# MainBoard_v1_4.net
KiCad netlist of a schematic drawn in EAGLE
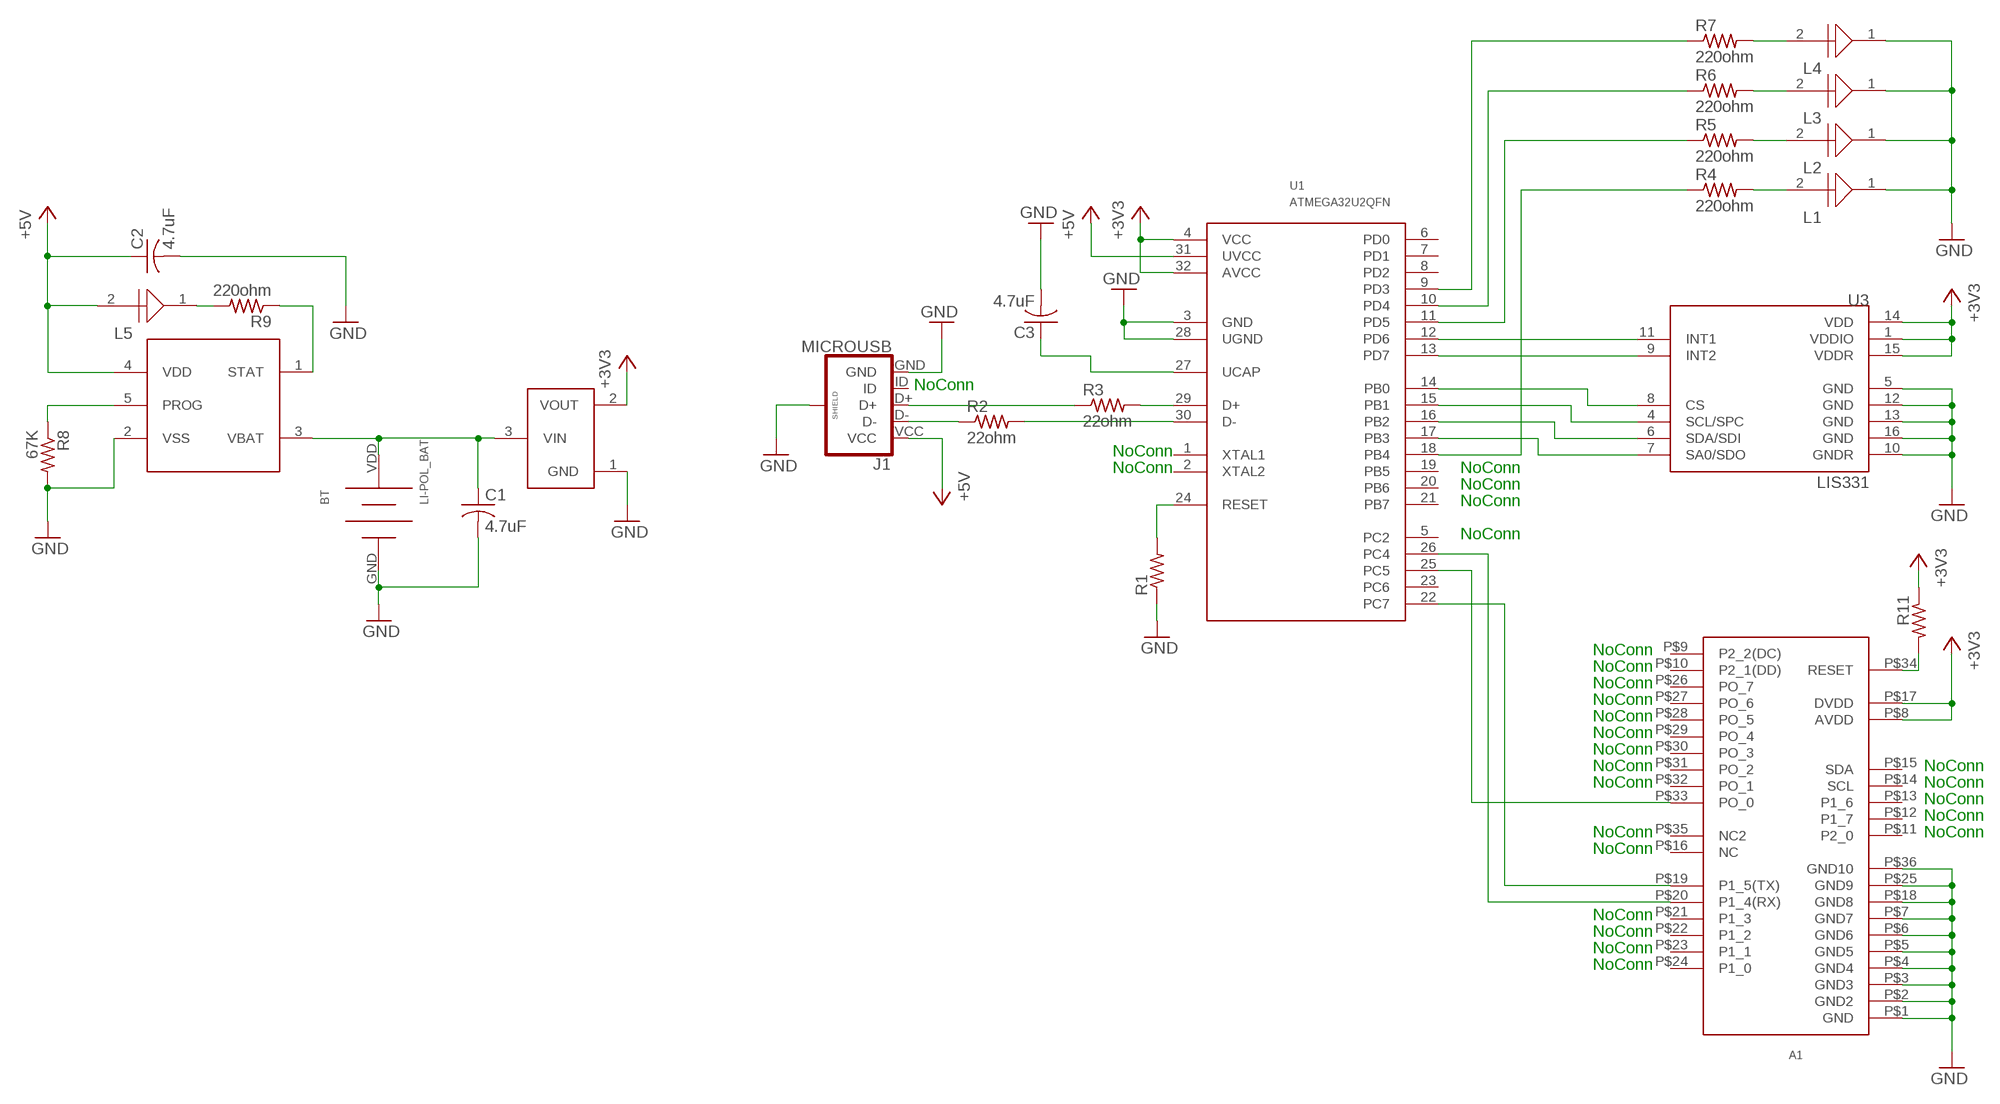
[diagram p0: schematic, sheet 1]

(export (version "E")
  (design (tool "Eeschema 10.0.6"))
  (components
    (comp (ref "A1")
      (value "BLE113-A")
      (footprint "eagle-import:BLUETOOTHNS")
      (libsource (lib "eagle-import") (part "BLE113-A"))
    )
    (comp (ref "BT")
      (value "LI-POL_BAT")
      (footprint "eagle-import:LI-POLY_28")
      (libsource (lib "eagle-import") (part "LI-POL_BAT"))
    )
    (comp (ref "C1")
      (value "4.7uF")
      (footprint "eagle-import:C0402")
      (libsource (lib "eagle-import") (part "C-USC0402"))
    )
    (comp (ref "C2")
      (value "4.7uF")
      (footprint "eagle-import:C0402")
      (libsource (lib "eagle-import") (part "C-USC0402"))
    )
    (comp (ref "C3")
      (value "4.7uF")
      (footprint "eagle-import:C0402")
      (libsource (lib "eagle-import") (part "C-USC0402"))
    )
    (comp (ref "J1")
      (value "MICROUSB")
      (footprint "eagle-import:MICROUSB")
      (libsource (lib "eagle-import") (part "MICROUSB"))
    )
    (comp (ref "L1")
      (value "LED_0402")
      (footprint "eagle-import:R0402")
      (libsource (lib "eagle-import") (part "LED_0402"))
    )
    (comp (ref "L2")
      (value "LED_0402")
      (footprint "eagle-import:R0402")
      (libsource (lib "eagle-import") (part "LED_0402"))
    )
    (comp (ref "L3")
      (value "LED_0402")
      (footprint "eagle-import:R0402")
      (libsource (lib "eagle-import") (part "LED_0402"))
    )
    (comp (ref "L4")
      (value "LED_0402")
      (footprint "eagle-import:R0402")
      (libsource (lib "eagle-import") (part "LED_0402"))
    )
    (comp (ref "L5")
      (value "LED_0402")
      (footprint "eagle-import:R0402")
      (libsource (lib "eagle-import") (part "LED_0402"))
    )
    (comp (ref "R1")
      (value "R-US_R0402")
      (footprint "eagle-import:R0402")
      (libsource (lib "eagle-import") (part "R-US_R0402"))
    )
    (comp (ref "R2")
      (value "22ohm")
      (footprint "eagle-import:R0402")
      (libsource (lib "eagle-import") (part "R-US_R0402"))
    )
    (comp (ref "R3")
      (value "22ohm")
      (footprint "eagle-import:R0402")
      (libsource (lib "eagle-import") (part "R-US_R0402"))
    )
    (comp (ref "R4")
      (value "220ohm")
      (footprint "eagle-import:R0402")
      (libsource (lib "eagle-import") (part "R-US_R0402"))
    )
    (comp (ref "R5")
      (value "220ohm")
      (footprint "eagle-import:R0402")
      (libsource (lib "eagle-import") (part "R-US_R0402"))
    )
    (comp (ref "R6")
      (value "220ohm")
      (footprint "eagle-import:R0402")
      (libsource (lib "eagle-import") (part "R-US_R0402"))
    )
    (comp (ref "R7")
      (value "220ohm")
      (footprint "eagle-import:R0402")
      (libsource (lib "eagle-import") (part "R-US_R0402"))
    )
    (comp (ref "R8")
      (value "67K")
      (footprint "eagle-import:R0402")
      (libsource (lib "eagle-import") (part "R-US_R0402"))
    )
    (comp (ref "R9")
      (value "220ohm")
      (footprint "eagle-import:R0402")
      (libsource (lib "eagle-import") (part "R-US_R0402"))
    )
    (comp (ref "R11")
      (value "R-US_R0402")
      (footprint "eagle-import:R0402")
      (libsource (lib "eagle-import") (part "R-US_R0402"))
    )
    (comp (ref "U1")
      (value "ATMEGA32U2QFN")
      (footprint "eagle-import:QFN-32")
      (libsource (lib "eagle-import") (part "ATMEGA32U2QFN"))
    )
    (comp (ref "U2")
      (value "MCP738312")
      (footprint "eagle-import:SOT23-5")
      (libsource (lib "eagle-import") (part "MCP738312"))
    )
    (comp (ref "U3")
      (value "LIS331")
      (footprint "eagle-import:LGA16-3MM")
      (libsource (lib "eagle-import") (part "LIS331"))
    )
    (comp (ref "U5")
      (value "REGULATOR")
      (footprint "eagle-import:SOT23-3")
      (libsource (lib "eagle-import") (part "REGULATOR"))
    )
  )
  (nets
    (net (code "1") (name "+3V3") (class "Default")
      (node (ref "A1") (pin "P$17") (pinfunction "DVDD_P$17") (pintype "bidirectional"))
      (node (ref "A1") (pin "P$8") (pinfunction "AVDD_P$8") (pintype "bidirectional"))
      (node (ref "R11") (pin "1") (pinfunction "1_1") (pintype "passive"))
      (node (ref "U1") (pin "32") (pinfunction "AVCC_32") (pintype "bidirectional"))
      (node (ref "U1") (pin "4") (pinfunction "VCC_4") (pintype "bidirectional"))
      (node (ref "U3") (pin "1") (pinfunction "VDDIO_1") (pintype "bidirectional"))
      (node (ref "U3") (pin "14") (pinfunction "VDD_14") (pintype "bidirectional"))
      (node (ref "U3") (pin "15") (pinfunction "VDDR_15") (pintype "bidirectional"))
      (node (ref "U5") (pin "2") (pinfunction "VOUT_2") (pintype "bidirectional"))
    )
    (net (code "2") (name "+5V") (class "Default")
      (node (ref "C2") (pin "1") (pinfunction "1_1") (pintype "passive"))
      (node (ref "J1") (pin "VCC") (pinfunction "VCC_VCC") (pintype "bidirectional"))
      (node (ref "L5") (pin "2") (pinfunction "P2_2") (pintype "bidirectional"))
      (node (ref "U1") (pin "31") (pinfunction "UVCC_31") (pintype "bidirectional"))
      (node (ref "U2") (pin "4") (pinfunction "VDD_4") (pintype "bidirectional"))
    )
    (net (code "3") (name "GND") (class "Default")
      (node (ref "A1") (pin "P$1") (pinfunction "GND_P$1") (pintype "bidirectional"))
      (node (ref "A1") (pin "P$18") (pinfunction "GND8_P$18") (pintype "bidirectional"))
      (node (ref "A1") (pin "P$2") (pinfunction "GND2_P$2") (pintype "bidirectional"))
      (node (ref "A1") (pin "P$25") (pinfunction "GND9_P$25") (pintype "bidirectional"))
      (node (ref "A1") (pin "P$3") (pinfunction "GND3_P$3") (pintype "bidirectional"))
      (node (ref "A1") (pin "P$36") (pinfunction "GND10_P$36") (pintype "bidirectional"))
      (node (ref "A1") (pin "P$4") (pinfunction "GND4_P$4") (pintype "bidirectional"))
      (node (ref "A1") (pin "P$5") (pinfunction "GND5_P$5") (pintype "bidirectional"))
      (node (ref "A1") (pin "P$6") (pinfunction "GND6_P$6") (pintype "bidirectional"))
      (node (ref "A1") (pin "P$7") (pinfunction "GND7_P$7") (pintype "bidirectional"))
      (node (ref "BT") (pin "GND") (pinfunction "GND_GND") (pintype "bidirectional"))
      (node (ref "C1") (pin "2") (pinfunction "2_2") (pintype "passive"))
      (node (ref "C2") (pin "2") (pinfunction "2_2") (pintype "passive"))
      (node (ref "C3") (pin "2") (pinfunction "2_2") (pintype "passive"))
      (node (ref "J1") (pin "GD1") (pinfunction "SHIELD_GD1") (pintype "bidirectional"))
      (node (ref "J1") (pin "GD2") (pinfunction "SHIELD_GD2") (pintype "bidirectional"))
      (node (ref "J1") (pin "GD3") (pinfunction "SHIELD_GD3") (pintype "bidirectional"))
      (node (ref "J1") (pin "GD4") (pinfunction "SHIELD_GD4") (pintype "bidirectional"))
      (node (ref "J1") (pin "GND") (pinfunction "GND_GND") (pintype "bidirectional"))
      (node (ref "L1") (pin "1") (pinfunction "P1_1") (pintype "bidirectional"))
      (node (ref "L2") (pin "1") (pinfunction "P1_1") (pintype "bidirectional"))
      (node (ref "L3") (pin "1") (pinfunction "P1_1") (pintype "bidirectional"))
      (node (ref "L4") (pin "1") (pinfunction "P1_1") (pintype "bidirectional"))
      (node (ref "R1") (pin "1") (pinfunction "1_1") (pintype "passive"))
      (node (ref "R8") (pin "2") (pinfunction "2_2") (pintype "passive"))
      (node (ref "U1") (pin "28") (pinfunction "UGND_28") (pintype "bidirectional"))
      (node (ref "U1") (pin "3") (pinfunction "GND_3") (pintype "bidirectional"))
      (node (ref "U2") (pin "2") (pinfunction "VSS_2") (pintype "bidirectional"))
      (node (ref "U3") (pin "10") (pinfunction "GNDR_10") (pintype "bidirectional"))
      (node (ref "U3") (pin "12") (pinfunction "GND_12") (pintype "bidirectional"))
      (node (ref "U3") (pin "13") (pinfunction "GND_13") (pintype "bidirectional"))
      (node (ref "U3") (pin "16") (pinfunction "GND_16") (pintype "bidirectional"))
      (node (ref "U3") (pin "5") (pinfunction "GND_5") (pintype "bidirectional"))
      (node (ref "U5") (pin "1") (pinfunction "GND_1") (pintype "bidirectional"))
    )
    (net (code "4") (name "Net-(A1-P1_4(RX))") (class "Default")
      (node (ref "A1") (pin "P$20") (pinfunction "P1_4(RX)_P$20") (pintype "bidirectional"))
      (node (ref "U1") (pin "26") (pinfunction "PC4_26") (pintype "bidirectional"))
    )
    (net (code "5") (name "Net-(A1-P1_5(TX))") (class "Default")
      (node (ref "A1") (pin "P$19") (pinfunction "P1_5(TX)_P$19") (pintype "bidirectional"))
      (node (ref "U1") (pin "22") (pinfunction "PC7_22") (pintype "bidirectional"))
    )
    (net (code "6") (name "Net-(A1-PO_0)") (class "Default")
      (node (ref "A1") (pin "P$33") (pinfunction "PO_0_P$33") (pintype "bidirectional"))
      (node (ref "U1") (pin "25") (pinfunction "PC5_25") (pintype "bidirectional"))
    )
    (net (code "7") (name "Net-(A1-RESET)") (class "Default")
      (node (ref "A1") (pin "P$34") (pinfunction "RESET_P$34") (pintype "bidirectional"))
      (node (ref "R11") (pin "2") (pinfunction "2_2") (pintype "passive"))
    )
    (net (code "8") (name "Net-(J1-PadD+)") (class "Default")
      (node (ref "J1") (pin "D+") (pinfunction "D+_D+") (pintype "bidirectional"))
      (node (ref "R3") (pin "1") (pinfunction "1_1") (pintype "passive"))
    )
    (net (code "9") (name "Net-(J1-PadD-)") (class "Default")
      (node (ref "J1") (pin "D-") (pinfunction "D-_D-") (pintype "bidirectional"))
      (node (ref "R2") (pin "1") (pinfunction "1_1") (pintype "passive"))
    )
    (net (code "10") (name "Net-(L1-P2)") (class "Default")
      (node (ref "L1") (pin "2") (pinfunction "P2_2") (pintype "bidirectional"))
      (node (ref "R4") (pin "2") (pinfunction "2_2") (pintype "passive"))
    )
    (net (code "11") (name "Net-(L2-P2)") (class "Default")
      (node (ref "L2") (pin "2") (pinfunction "P2_2") (pintype "bidirectional"))
      (node (ref "R5") (pin "2") (pinfunction "2_2") (pintype "passive"))
    )
    (net (code "12") (name "Net-(L3-P2)") (class "Default")
      (node (ref "L3") (pin "2") (pinfunction "P2_2") (pintype "bidirectional"))
      (node (ref "R6") (pin "2") (pinfunction "2_2") (pintype "passive"))
    )
    (net (code "13") (name "Net-(L4-P2)") (class "Default")
      (node (ref "L4") (pin "2") (pinfunction "P2_2") (pintype "bidirectional"))
      (node (ref "R7") (pin "2") (pinfunction "2_2") (pintype "passive"))
    )
    (net (code "14") (name "Net-(L5-P1)") (class "Default")
      (node (ref "L5") (pin "1") (pinfunction "P1_1") (pintype "bidirectional"))
      (node (ref "R9") (pin "2") (pinfunction "2_2") (pintype "passive"))
    )
    (net (code "15") (name "Net-(U1-D+)") (class "Default")
      (node (ref "R3") (pin "2") (pinfunction "2_2") (pintype "passive"))
      (node (ref "U1") (pin "29") (pinfunction "D+_29") (pintype "bidirectional"))
    )
    (net (code "16") (name "Net-(U1-D-)") (class "Default")
      (node (ref "R2") (pin "2") (pinfunction "2_2") (pintype "passive"))
      (node (ref "U1") (pin "30") (pinfunction "D-_30") (pintype "bidirectional"))
    )
    (net (code "17") (name "Net-(U1-PB0)") (class "Default")
      (node (ref "U1") (pin "14") (pinfunction "PB0_14") (pintype "bidirectional"))
      (node (ref "U3") (pin "8") (pinfunction "CS_8") (pintype "bidirectional"))
    )
    (net (code "18") (name "Net-(U1-PB1)") (class "Default")
      (node (ref "U1") (pin "15") (pinfunction "PB1_15") (pintype "bidirectional"))
      (node (ref "U3") (pin "4") (pinfunction "SCL/SPC_4") (pintype "bidirectional"))
    )
    (net (code "19") (name "Net-(U1-PB2)") (class "Default")
      (node (ref "U1") (pin "16") (pinfunction "PB2_16") (pintype "bidirectional"))
      (node (ref "U3") (pin "6") (pinfunction "SDA/SDI_6") (pintype "bidirectional"))
    )
    (net (code "20") (name "Net-(U1-PB3)") (class "Default")
      (node (ref "U1") (pin "17") (pinfunction "PB3_17") (pintype "bidirectional"))
      (node (ref "U3") (pin "7") (pinfunction "SA0/SDO_7") (pintype "bidirectional"))
    )
    (net (code "21") (name "Net-(U1-PB4)") (class "Default")
      (node (ref "R4") (pin "1") (pinfunction "1_1") (pintype "passive"))
      (node (ref "U1") (pin "18") (pinfunction "PB4_18") (pintype "bidirectional"))
    )
    (net (code "22") (name "Net-(U1-PD3)") (class "Default")
      (node (ref "R7") (pin "1") (pinfunction "1_1") (pintype "passive"))
      (node (ref "U1") (pin "9") (pinfunction "PD3_9") (pintype "bidirectional"))
    )
    (net (code "23") (name "Net-(U1-PD4)") (class "Default")
      (node (ref "R6") (pin "1") (pinfunction "1_1") (pintype "passive"))
      (node (ref "U1") (pin "10") (pinfunction "PD4_10") (pintype "bidirectional"))
    )
    (net (code "24") (name "Net-(U1-PD5)") (class "Default")
      (node (ref "R5") (pin "1") (pinfunction "1_1") (pintype "passive"))
      (node (ref "U1") (pin "11") (pinfunction "PD5_11") (pintype "bidirectional"))
    )
    (net (code "25") (name "Net-(U1-PD6)") (class "Default")
      (node (ref "U1") (pin "12") (pinfunction "PD6_12") (pintype "bidirectional"))
      (node (ref "U3") (pin "11") (pinfunction "INT1_11") (pintype "bidirectional"))
    )
    (net (code "26") (name "Net-(U1-PD7)") (class "Default")
      (node (ref "U1") (pin "13") (pinfunction "PD7_13") (pintype "bidirectional"))
      (node (ref "U3") (pin "9") (pinfunction "INT2_9") (pintype "bidirectional"))
    )
    (net (code "27") (name "Net-(U1-RESET)") (class "Default")
      (node (ref "R1") (pin "2") (pinfunction "2_2") (pintype "passive"))
      (node (ref "U1") (pin "24") (pinfunction "RESET_24") (pintype "bidirectional"))
    )
    (net (code "28") (name "Net-(U1-UCAP)") (class "Default")
      (node (ref "C3") (pin "1") (pinfunction "1_1") (pintype "passive"))
      (node (ref "U1") (pin "27") (pinfunction "UCAP_27") (pintype "bidirectional"))
    )
    (net (code "29") (name "Net-(U2-PROG)") (class "Default")
      (node (ref "R8") (pin "1") (pinfunction "1_1") (pintype "passive"))
      (node (ref "U2") (pin "5") (pinfunction "PROG_5") (pintype "bidirectional"))
    )
    (net (code "30") (name "Net-(U2-STAT)") (class "Default")
      (node (ref "R9") (pin "1") (pinfunction "1_1") (pintype "passive"))
      (node (ref "U2") (pin "1") (pinfunction "STAT_1") (pintype "bidirectional"))
    )
    (net (code "31") (name "Net-(U2-VBAT)") (class "Default")
      (node (ref "BT") (pin "VDD") (pinfunction "VDD_VDD") (pintype "bidirectional"))
      (node (ref "C1") (pin "1") (pinfunction "1_1") (pintype "passive"))
      (node (ref "U2") (pin "3") (pinfunction "VBAT_3") (pintype "bidirectional"))
      (node (ref "U5") (pin "3") (pinfunction "VIN_3") (pintype "bidirectional"))
    )
    (net (code "32") (name "unconnected-(A1-NC-PadP$16)") (class "Default")
      (node (ref "A1") (pin "P$16") (pinfunction "NC_P$16") (pintype "bidirectional"))
    )
    (net (code "33") (name "unconnected-(A1-NC2-PadP$35)") (class "Default")
      (node (ref "A1") (pin "P$35") (pinfunction "NC2_P$35") (pintype "bidirectional"))
    )
    (net (code "34") (name "unconnected-(A1-P1_0-PadP$24)") (class "Default")
      (node (ref "A1") (pin "P$24") (pinfunction "P1_0_P$24") (pintype "bidirectional"))
    )
    (net (code "35") (name "unconnected-(A1-P1_1-PadP$23)") (class "Default")
      (node (ref "A1") (pin "P$23") (pinfunction "P1_1_P$23") (pintype "bidirectional"))
    )
    (net (code "36") (name "unconnected-(A1-P1_2-PadP$22)") (class "Default")
      (node (ref "A1") (pin "P$22") (pinfunction "P1_2_P$22") (pintype "bidirectional"))
    )
    (net (code "37") (name "unconnected-(A1-P1_3-PadP$21)") (class "Default")
      (node (ref "A1") (pin "P$21") (pinfunction "P1_3_P$21") (pintype "bidirectional"))
    )
    (net (code "38") (name "unconnected-(A1-P1_6-PadP$13)") (class "Default")
      (node (ref "A1") (pin "P$13") (pinfunction "P1_6_P$13") (pintype "bidirectional"))
    )
    (net (code "39") (name "unconnected-(A1-P1_7-PadP$12)") (class "Default")
      (node (ref "A1") (pin "P$12") (pinfunction "P1_7_P$12") (pintype "bidirectional"))
    )
    (net (code "40") (name "unconnected-(A1-P2_0-PadP$11)") (class "Default")
      (node (ref "A1") (pin "P$11") (pinfunction "P2_0_P$11") (pintype "bidirectional"))
    )
    (net (code "41") (name "unconnected-(A1-P2_1(DD)-PadP$10)") (class "Default")
      (node (ref "A1") (pin "P$10") (pinfunction "P2_1(DD)_P$10") (pintype "bidirectional"))
    )
    (net (code "42") (name "unconnected-(A1-P2_2(DC)-PadP$9)") (class "Default")
      (node (ref "A1") (pin "P$9") (pinfunction "P2_2(DC)_P$9") (pintype "bidirectional"))
    )
    (net (code "43") (name "unconnected-(A1-PO_1-PadP$32)") (class "Default")
      (node (ref "A1") (pin "P$32") (pinfunction "PO_1_P$32") (pintype "bidirectional"))
    )
    (net (code "44") (name "unconnected-(A1-PO_2-PadP$31)") (class "Default")
      (node (ref "A1") (pin "P$31") (pinfunction "PO_2_P$31") (pintype "bidirectional"))
    )
    (net (code "45") (name "unconnected-(A1-PO_3-PadP$30)") (class "Default")
      (node (ref "A1") (pin "P$30") (pinfunction "PO_3_P$30") (pintype "bidirectional"))
    )
    (net (code "46") (name "unconnected-(A1-PO_4-PadP$29)") (class "Default")
      (node (ref "A1") (pin "P$29") (pinfunction "PO_4_P$29") (pintype "bidirectional"))
    )
    (net (code "47") (name "unconnected-(A1-PO_5-PadP$28)") (class "Default")
      (node (ref "A1") (pin "P$28") (pinfunction "PO_5_P$28") (pintype "bidirectional"))
    )
    (net (code "48") (name "unconnected-(A1-PO_6-PadP$27)") (class "Default")
      (node (ref "A1") (pin "P$27") (pinfunction "PO_6_P$27") (pintype "bidirectional"))
    )
    (net (code "49") (name "unconnected-(A1-PO_7-PadP$26)") (class "Default")
      (node (ref "A1") (pin "P$26") (pinfunction "PO_7_P$26") (pintype "bidirectional"))
    )
    (net (code "50") (name "unconnected-(A1-SCL-PadP$14)") (class "Default")
      (node (ref "A1") (pin "P$14") (pinfunction "SCL_P$14") (pintype "bidirectional"))
    )
    (net (code "51") (name "unconnected-(A1-SDA-PadP$15)") (class "Default")
      (node (ref "A1") (pin "P$15") (pinfunction "SDA_P$15") (pintype "bidirectional"))
    )
    (net (code "52") (name "unconnected-(J1-PadID)") (class "Default")
      (node (ref "J1") (pin "ID") (pinfunction "ID_ID") (pintype "bidirectional"))
    )
    (net (code "53") (name "unconnected-(U1-PB5-Pad19)") (class "Default")
      (node (ref "U1") (pin "19") (pinfunction "PB5_19") (pintype "bidirectional"))
    )
    (net (code "54") (name "unconnected-(U1-PB6-Pad20)") (class "Default")
      (node (ref "U1") (pin "20") (pinfunction "PB6_20") (pintype "bidirectional"))
    )
    (net (code "55") (name "unconnected-(U1-PB7-Pad21)") (class "Default")
      (node (ref "U1") (pin "21") (pinfunction "PB7_21") (pintype "bidirectional"))
    )
    (net (code "56") (name "unconnected-(U1-PC2-Pad5)") (class "Default")
      (node (ref "U1") (pin "5") (pinfunction "PC2_5") (pintype "bidirectional"))
    )
    (net (code "57") (name "unconnected-(U1-PC6-Pad23)") (class "Default")
      (node (ref "U1") (pin "23") (pinfunction "PC6_23") (pintype "bidirectional"))
    )
    (net (code "58") (name "unconnected-(U1-PD0-Pad6)") (class "Default")
      (node (ref "U1") (pin "6") (pinfunction "PD0_6") (pintype "bidirectional"))
    )
    (net (code "59") (name "unconnected-(U1-PD1-Pad7)") (class "Default")
      (node (ref "U1") (pin "7") (pinfunction "PD1_7") (pintype "bidirectional"))
    )
    (net (code "60") (name "unconnected-(U1-PD2-Pad8)") (class "Default")
      (node (ref "U1") (pin "8") (pinfunction "PD2_8") (pintype "bidirectional"))
    )
    (net (code "61") (name "unconnected-(U1-XTAL1-Pad1)") (class "Default")
      (node (ref "U1") (pin "1") (pinfunction "XTAL1_1") (pintype "bidirectional"))
    )
    (net (code "62") (name "unconnected-(U1-XTAL2-Pad2)") (class "Default")
      (node (ref "U1") (pin "2") (pinfunction "XTAL2_2") (pintype "bidirectional"))
    )
  )
)
